# TB_Microcontroller.net
KiCad netlist of a schematic drawn in Altium Designer
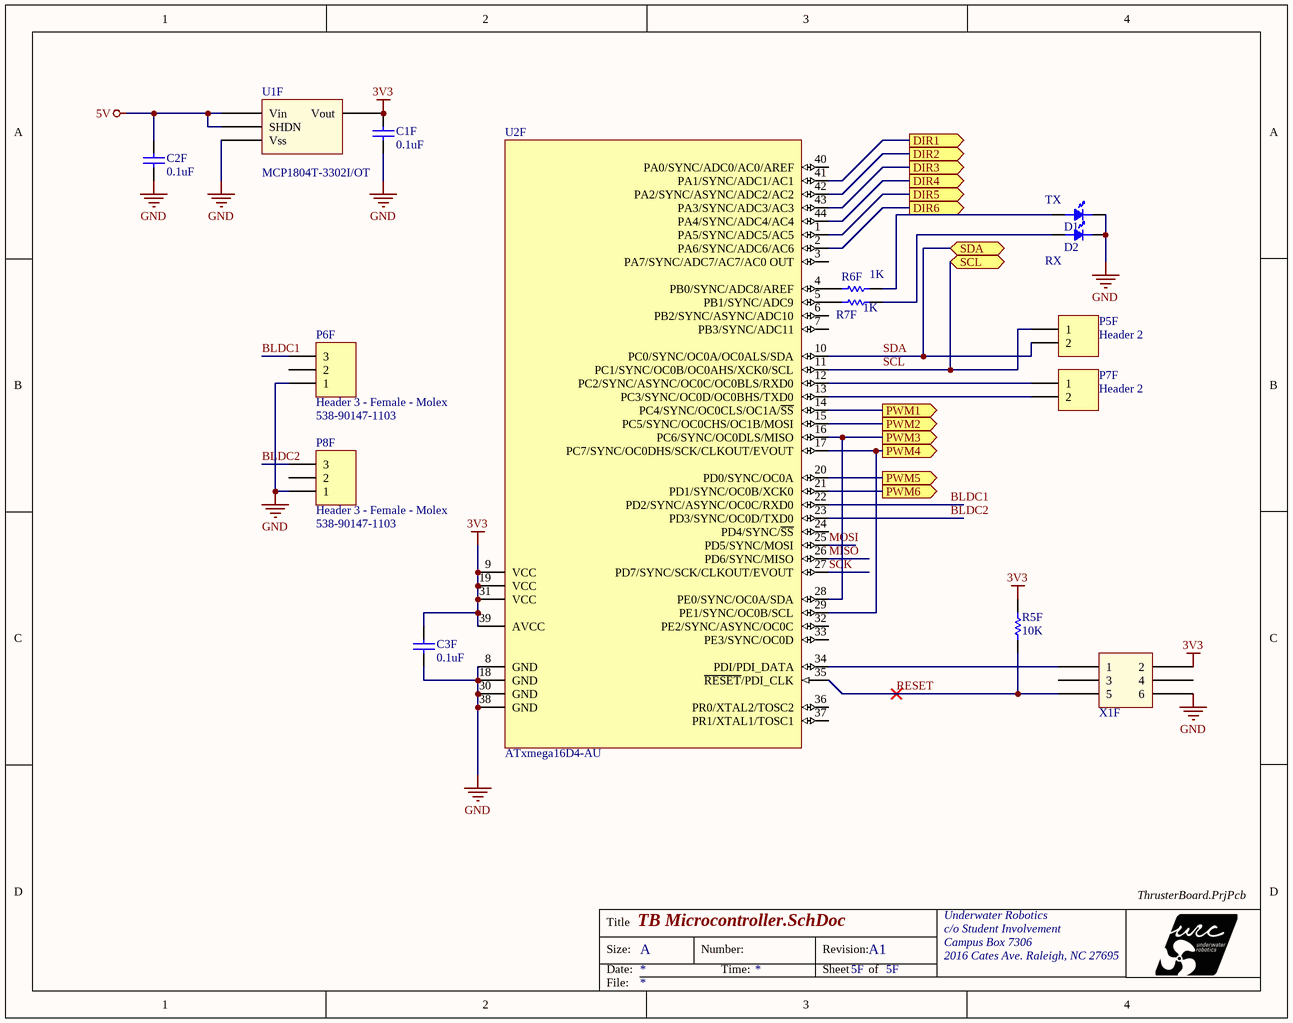
[diagram p0: TB Microcontroller.SchDoc]

(export (version "E")
  (design (tool "Eeschema 10.0.6"))
  (components
    (comp (ref "C1F")
      (value "0.1uF")
      (footprint "C0603")
      (description "Ceramic MLCC, Multicompo, X7R Dielectric")
      (fields
        (field (name "MANUFACTURER PART NUMBER") "MC0603B104K500CT")
        (field (name "Comment") "0.1uF, C0603, MultiComp")
      )
      (libsource (lib "Capacitors SchLib") (part "0.1uF, C0603, MultiComp"))
    )
    (comp (ref "C2F")
      (value "0.1uF")
      (footprint "C0603")
      (description "Ceramic MLCC, Multicompo, X7R Dielectric")
      (fields
        (field (name "MANUFACTURER PART NUMBER") "MC0603B104K500CT")
        (field (name "Comment") "0.1uF, C0603, MultiComp")
      )
      (libsource (lib "Capacitors SchLib") (part "0.1uF, C0603, MultiComp"))
    )
    (comp (ref "C3F")
      (value "0.1uF")
      (footprint "C0603")
      (description "Ceramic MLCC, Multicompo, X7R Dielectric")
      (fields
        (field (name "MANUFACTURER PART NUMBER") "MC0603B104K500CT")
        (field (name "Comment") "0.1uF, C0603, MultiComp")
      )
      (libsource (lib "Capacitors SchLib") (part "0.1uF, C0603, MultiComp"))
    )
    (comp (ref "D1") (value "LED") (footprint "LED0805") (libsource (lib "URC_Lib") (part "LED")))
    (comp (ref "D2") (value "LED") (footprint "LED0805") (libsource (lib "URC_Lib") (part "LED")))
    (comp (ref "P5F")
      (value "Header 2")
      (footprint "HDR1X2")
      (description "Header, 2-Pin")
      (fields (field (name "PUBLISHER") "Altium Limited"))
      (libsource (lib "Miscellaneous Connectors") (part "Header 2"))
    )
    (comp (ref "P6F")
      (value "Header 3 - Female - Molex")
      (footprint "HDR1X3 - Female - Molex")
      (description "Header, 3-Pin")
      (fields
        (field (name "MANUFACTURER") "Molex")
        (field (name "MANUFACTURER PART NUMBER") "90147-1103")
        (field (name "SUPPLIER PART NUMBER 1") "538-90147-1103")
      )
      (libsource (lib "URC_Lib") (part "Header 3 - Female - Molex"))
    )
    (comp (ref "P7F")
      (value "Header 2")
      (footprint "HDR1X2")
      (description "Header, 2-Pin")
      (fields (field (name "PUBLISHER") "Altium Limited"))
      (libsource (lib "Miscellaneous Connectors") (part "Header 2"))
    )
    (comp (ref "P8F")
      (value "Header 3 - Female - Molex")
      (footprint "HDR1X3 - Female - Molex")
      (description "Header, 3-Pin")
      (fields
        (field (name "MANUFACTURER") "Molex")
        (field (name "MANUFACTURER PART NUMBER") "90147-1103")
        (field (name "SUPPLIER PART NUMBER 1") "538-90147-1103")
      )
      (libsource (lib "URC_Lib") (part "Header 3 - Female - Molex"))
    )
    (comp (ref "R5F")
      (value "10K")
      (footprint "R0603")
      (description "Resistor")
      (fields (field (name "TOLERANCE") "1%") (field (name "MANUFACTURER PART NUMBER") "RC0603FR-1010KL"))
      (libsource (lib "Resistors SchLib") (part "10k, 1%, 100mW, Yageo, R0603"))
    )
    (comp (ref "R6F")
      (value "1K")
      (footprint "R0603")
      (description "Resistor")
      (fields (field (name "TOLERANCE") "5%") (field (name "MANUFACTURER PART NUMBER") "RC0603JR-131KL"))
      (libsource (lib "Resistors SchLib") (part "1k, 5%, 100mW, Yageo, R0603"))
    )
    (comp (ref "R7F")
      (value "1K")
      (footprint "R0603")
      (description "Resistor")
      (fields (field (name "TOLERANCE") "5%") (field (name "MANUFACTURER PART NUMBER") "RC0603JR-131KL"))
      (libsource (lib "Resistors SchLib") (part "1k, 5%, 100mW, Yageo, R0603"))
    )
    (comp (ref "U1F")
      (value "MCP1804T-3302I/OT")
      (footprint "MCP1804T-3302I/OT")
      (description "3.3V Linear Regulator")
      (fields (field (name "MANUFACTURER PART NUMBER") "MCP1804T-3302I/OT"))
      (libsource (lib "URC") (part "MCP1804T-3302I/OT"))
    )
    (comp (ref "U2F")
      (value "ATxmega16D4-AU")
      (footprint "44A_N")
      (fields (field (name "MANUFACTURER PART NUMBER") "ATXMEGA16D4-AU"))
      (libsource (lib "Atmel Microcontroller AVR XMEGA") (part "ATxmega16D4-AU"))
    )
    (comp (ref "X1F")
      (value "Header")
      (footprint "2x3 Header")
      (description "2x3 Header")
      (fields (field (name "MANUFACTURER PART NUMBER") "67996-406HLF"))
      (libsource (lib "URC") (part "2x3 Header"))
    )
  )
  (nets
    (net (code "1") (name "/BLDC1") (class "Default")
      (node (ref "P6F") (pin "3") (pinfunction "3_3") (pintype "passive"))
      (node (ref "U2F") (pin "22") (pinfunction "PD2/SYNC/ASYNC/OC0C/RXD0_22") (pintype "bidirectional"))
    )
    (net (code "2") (name "/BLDC2") (class "Default")
      (node (ref "P8F") (pin "3") (pinfunction "3_3") (pintype "passive"))
      (node (ref "U2F") (pin "23") (pinfunction "PD3/SYNC/OC0D/TXD0_23") (pintype "bidirectional"))
    )
    (net (code "3") (name "/DIR1") (class "Default")
      (node (ref "U2F") (pin "41") (pinfunction "PA1/SYNC/ADC1/AC1_41") (pintype "bidirectional"))
    )
    (net (code "4") (name "/DIR2") (class "Default")
      (node (ref "U2F") (pin "42") (pinfunction "PA2/SYNC/ASYNC/ADC2/AC2_42") (pintype "bidirectional"))
    )
    (net (code "5") (name "/DIR3") (class "Default")
      (node (ref "U2F") (pin "43") (pinfunction "PA3/SYNC/ADC3/AC3_43") (pintype "bidirectional"))
    )
    (net (code "6") (name "/DIR4") (class "Default")
      (node (ref "U2F") (pin "44") (pinfunction "PA4/SYNC/ADC4/AC4_44") (pintype "bidirectional"))
    )
    (net (code "7") (name "/DIR5") (class "Default")
      (node (ref "U2F") (pin "1") (pinfunction "PA5/SYNC/ADC5/AC5_1") (pintype "bidirectional"))
    )
    (net (code "8") (name "/DIR6") (class "Default")
      (node (ref "U2F") (pin "2") (pinfunction "PA6/SYNC/ADC6/AC6_2") (pintype "bidirectional"))
    )
    (net (code "9") (name "/MISO") (class "Default")
      (node (ref "U2F") (pin "26") (pinfunction "PD6/SYNC/MISO_26") (pintype "bidirectional"))
    )
    (net (code "10") (name "/MOSI") (class "Default")
      (node (ref "U2F") (pin "25") (pinfunction "PD5/SYNC/MOSI_25") (pintype "bidirectional"))
    )
    (net (code "11") (name "/PWM1") (class "Default")
      (node (ref "U2F") (pin "14") (pinfunction "PC4/SYNC/OC0CLS/OC1A/~{SS}_14") (pintype "bidirectional"))
    )
    (net (code "12") (name "/PWM2") (class "Default")
      (node (ref "U2F") (pin "15") (pinfunction "PC5/SYNC/OC0CHS/OC1B/MOSI_15") (pintype "bidirectional"))
    )
    (net (code "13") (name "/PWM3") (class "Default")
      (node (ref "U2F") (pin "16") (pinfunction "PC6/SYNC/OC0DLS/MISO_16") (pintype "bidirectional"))
      (node (ref "U2F") (pin "28") (pinfunction "PE0/SYNC/OC0A/SDA_28") (pintype "bidirectional"))
    )
    (net (code "14") (name "/PWM4") (class "Default")
      (node (ref "U2F") (pin "17") (pinfunction "PC7/SYNC/OC0DHS/SCK/CLKOUT/EVOUT_17") (pintype "bidirectional"))
      (node (ref "U2F") (pin "29") (pinfunction "PE1/SYNC/OC0B/SCL_29") (pintype "bidirectional"))
    )
    (net (code "15") (name "/PWM5") (class "Default")
      (node (ref "U2F") (pin "20") (pinfunction "PD0/SYNC/OC0A_20") (pintype "bidirectional"))
    )
    (net (code "16") (name "/PWM6") (class "Default")
      (node (ref "U2F") (pin "21") (pinfunction "PD1/SYNC/OC0B/XCK0_21") (pintype "bidirectional"))
    )
    (net (code "18") (name "/SCK") (class "Default")
      (node (ref "U2F") (pin "27") (pinfunction "PD7/SYNC/SCK/CLKOUT/EVOUT_27") (pintype "bidirectional"))
    )
    (net (code "19") (name "/SCL") (class "Default")
      (node (ref "P5F") (pin "1") (pinfunction "1_1") (pintype "passive"))
      (node (ref "U2F") (pin "11") (pinfunction "PC1/SYNC/OC0B/OC0AHS/XCK0/SCL_11") (pintype "bidirectional"))
    )
    (net (code "20") (name "/SDA") (class "Default")
      (node (ref "P5F") (pin "2") (pinfunction "2_2") (pintype "passive"))
      (node (ref "U2F") (pin "10") (pinfunction "PC0/SYNC/OC0A/OC0ALS/SDA_10") (pintype "bidirectional"))
    )
    (net (code "21") (name "3V3") (class "Default")
      (node (ref "C1F") (pin "1") (pinfunction "+_1") (pintype "passive"))
      (node (ref "C3F") (pin "1") (pinfunction "+_1") (pintype "passive"))
      (node (ref "R5F") (pin "2") (pinfunction "2_2") (pintype "passive"))
      (node (ref "U1F") (pin "Vout") (pinfunction "Vout_Vout") (pintype "passive"))
      (node (ref "U2F") (pin "19") (pinfunction "VCC_19") (pintype "power_in"))
      (node (ref "U2F") (pin "31") (pinfunction "VCC_31") (pintype "power_in"))
      (node (ref "U2F") (pin "39") (pinfunction "AVCC_39") (pintype "power_in"))
      (node (ref "U2F") (pin "9") (pinfunction "VCC_9") (pintype "power_in"))
      (node (ref "X1F") (pin "2") (pinfunction "2_2") (pintype "passive"))
    )
    (net (code "22") (name "5V") (class "Default")
      (node (ref "C2F") (pin "1") (pinfunction "+_1") (pintype "passive"))
      (node (ref "U1F") (pin "SHDN") (pinfunction "SHDN_SHDN") (pintype "passive"))
      (node (ref "U1F") (pin "Vin") (pinfunction "Vin_Vin") (pintype "passive"))
    )
    (net (code "23") (name "GND") (class "Default")
      (node (ref "C1F") (pin "2") (pinfunction "2_2") (pintype "passive"))
      (node (ref "C2F") (pin "2") (pinfunction "2_2") (pintype "passive"))
      (node (ref "C3F") (pin "2") (pinfunction "2_2") (pintype "passive"))
      (node (ref "D1") (pin "1") (pinfunction "1_1") (pintype "passive"))
      (node (ref "D2") (pin "1") (pinfunction "1_1") (pintype "passive"))
      (node (ref "P6F") (pin "1") (pinfunction "1_1") (pintype "passive"))
      (node (ref "P8F") (pin "1") (pinfunction "1_1") (pintype "passive"))
      (node (ref "U1F") (pin "Vss") (pinfunction "Vss_Vss") (pintype "passive"))
      (node (ref "U2F") (pin "18") (pinfunction "GND_18") (pintype "power_in"))
      (node (ref "U2F") (pin "30") (pinfunction "GND_30") (pintype "power_in"))
      (node (ref "U2F") (pin "38") (pinfunction "GND_38") (pintype "power_in"))
      (node (ref "U2F") (pin "8") (pinfunction "GND_8") (pintype "power_in"))
      (node (ref "X1F") (pin "6") (pinfunction "6_6") (pintype "passive"))
    )
    (net (code "24") (name "Net-(D1-Pad2)") (class "Default")
      (node (ref "D1") (pin "2") (pinfunction "2_2") (pintype "passive"))
      (node (ref "R6F") (pin "2") (pinfunction "2_2") (pintype "passive"))
    )
    (net (code "25") (name "Net-(D2-Pad2)") (class "Default")
      (node (ref "D2") (pin "2") (pinfunction "2_2") (pintype "passive"))
      (node (ref "R7F") (pin "2") (pinfunction "2_2") (pintype "passive"))
    )
    (net (code "26") (name "Net-(U2F-PB0{slash}SYNC{slash}ADC8{slash}AREF)") (class "Default")
      (node (ref "R6F") (pin "1") (pinfunction "1_1") (pintype "passive"))
      (node (ref "U2F") (pin "4") (pinfunction "PB0/SYNC/ADC8/AREF_4") (pintype "bidirectional"))
    )
    (net (code "27") (name "Net-(U2F-PB1{slash}SYNC{slash}ADC9)") (class "Default")
      (node (ref "R7F") (pin "1") (pinfunction "1_1") (pintype "passive"))
      (node (ref "U2F") (pin "5") (pinfunction "PB1/SYNC/ADC9_5") (pintype "bidirectional"))
    )
    (net (code "28") (name "Net-(U2F-PC2{slash}SYNC{slash}ASYNC{slash}OC0C{slash}OC0BLS{slash}RXD0)") (class "Default")
      (node (ref "P7F") (pin "1") (pinfunction "1_1") (pintype "passive"))
      (node (ref "U2F") (pin "12") (pinfunction "PC2/SYNC/ASYNC/OC0C/OC0BLS/RXD0_12") (pintype "bidirectional"))
    )
    (net (code "29") (name "Net-(U2F-PC3{slash}SYNC{slash}OC0D{slash}OC0BHS{slash}TXD0)") (class "Default")
      (node (ref "P7F") (pin "2") (pinfunction "2_2") (pintype "passive"))
      (node (ref "U2F") (pin "13") (pinfunction "PC3/SYNC/OC0D/OC0BHS/TXD0_13") (pintype "bidirectional"))
    )
    (net (code "30") (name "Net-(U2F-PDI{slash}PDI_DATA)") (class "Default")
      (node (ref "U2F") (pin "34") (pinfunction "PDI/PDI_DATA_34") (pintype "bidirectional"))
      (node (ref "X1F") (pin "1") (pinfunction "1_1") (pintype "passive"))
    )
    (net (code "31") (name "Net-(U2F-~{RESET}{slash}PDI_CLK)") (class "Default")
      (node (ref "R5F") (pin "1") (pinfunction "1_1") (pintype "passive"))
      (node (ref "U2F") (pin "35") (pinfunction "~{RESET}/PDI_CLK_35") (pintype "input"))
      (node (ref "X1F") (pin "5") (pinfunction "5_5") (pintype "passive"))
    )
    (net (code "32") (name "unconnected-(P6F-Pad2)") (class "Default")
      (node (ref "P6F") (pin "2") (pinfunction "2_2") (pintype "passive"))
    )
    (net (code "33") (name "unconnected-(P8F-Pad2)") (class "Default")
      (node (ref "P8F") (pin "2") (pinfunction "2_2") (pintype "passive"))
    )
    (net (code "34") (name "unconnected-(U2F-PA0{slash}SYNC{slash}ADC0{slash}AC0{slash}AREF-Pad40)") (class "Default")
      (node (ref "U2F") (pin "40") (pinfunction "PA0/SYNC/ADC0/AC0/AREF_40") (pintype "bidirectional"))
    )
    (net (code "35") (name "unconnected-(U2F-PA7{slash}SYNC{slash}ADC7{slash}AC7{slash}AC0_OUT-Pad3)") (class "Default")
      (node (ref "U2F") (pin "3") (pinfunction "PA7/SYNC/ADC7/AC7/AC0_OUT_3") (pintype "bidirectional"))
    )
    (net (code "36") (name "unconnected-(U2F-PB2{slash}SYNC{slash}ASYNC{slash}ADC10-Pad6)") (class "Default")
      (node (ref "U2F") (pin "6") (pinfunction "PB2/SYNC/ASYNC/ADC10_6") (pintype "bidirectional"))
    )
    (net (code "37") (name "unconnected-(U2F-PB3{slash}SYNC{slash}ADC11-Pad7)") (class "Default")
      (node (ref "U2F") (pin "7") (pinfunction "PB3/SYNC/ADC11_7") (pintype "bidirectional"))
    )
    (net (code "38") (name "unconnected-(U2F-PD4{slash}SYNC{slash}~{SS}-Pad24)") (class "Default")
      (node (ref "U2F") (pin "24") (pinfunction "PD4/SYNC/~{SS}_24") (pintype "bidirectional"))
    )
    (net (code "39") (name "unconnected-(U2F-PE2{slash}SYNC{slash}ASYNC{slash}OC0C-Pad32)") (class "Default")
      (node (ref "U2F") (pin "32") (pinfunction "PE2/SYNC/ASYNC/OC0C_32") (pintype "bidirectional"))
    )
    (net (code "40") (name "unconnected-(U2F-PE3{slash}SYNC{slash}OC0D-Pad33)") (class "Default")
      (node (ref "U2F") (pin "33") (pinfunction "PE3/SYNC/OC0D_33") (pintype "bidirectional"))
    )
    (net (code "41") (name "unconnected-(U2F-PR0{slash}XTAL2{slash}TOSC2-Pad36)") (class "Default")
      (node (ref "U2F") (pin "36") (pinfunction "PR0/XTAL2/TOSC2_36") (pintype "bidirectional"))
    )
    (net (code "42") (name "unconnected-(U2F-PR1{slash}XTAL1{slash}TOSC1-Pad37)") (class "Default")
      (node (ref "U2F") (pin "37") (pinfunction "PR1/XTAL1/TOSC1_37") (pintype "bidirectional"))
    )
    (net (code "43") (name "unconnected-(X1F-Pad3)") (class "Default")
      (node (ref "X1F") (pin "3") (pinfunction "3_3") (pintype "passive"))
    )
    (net (code "44") (name "unconnected-(X1F-Pad4)") (class "Default")
      (node (ref "X1F") (pin "4") (pinfunction "4_4") (pintype "passive"))
    )
  )
)
